# TiltMouseThroughHole.net
KiCad netlist of a schematic drawn in EAGLE
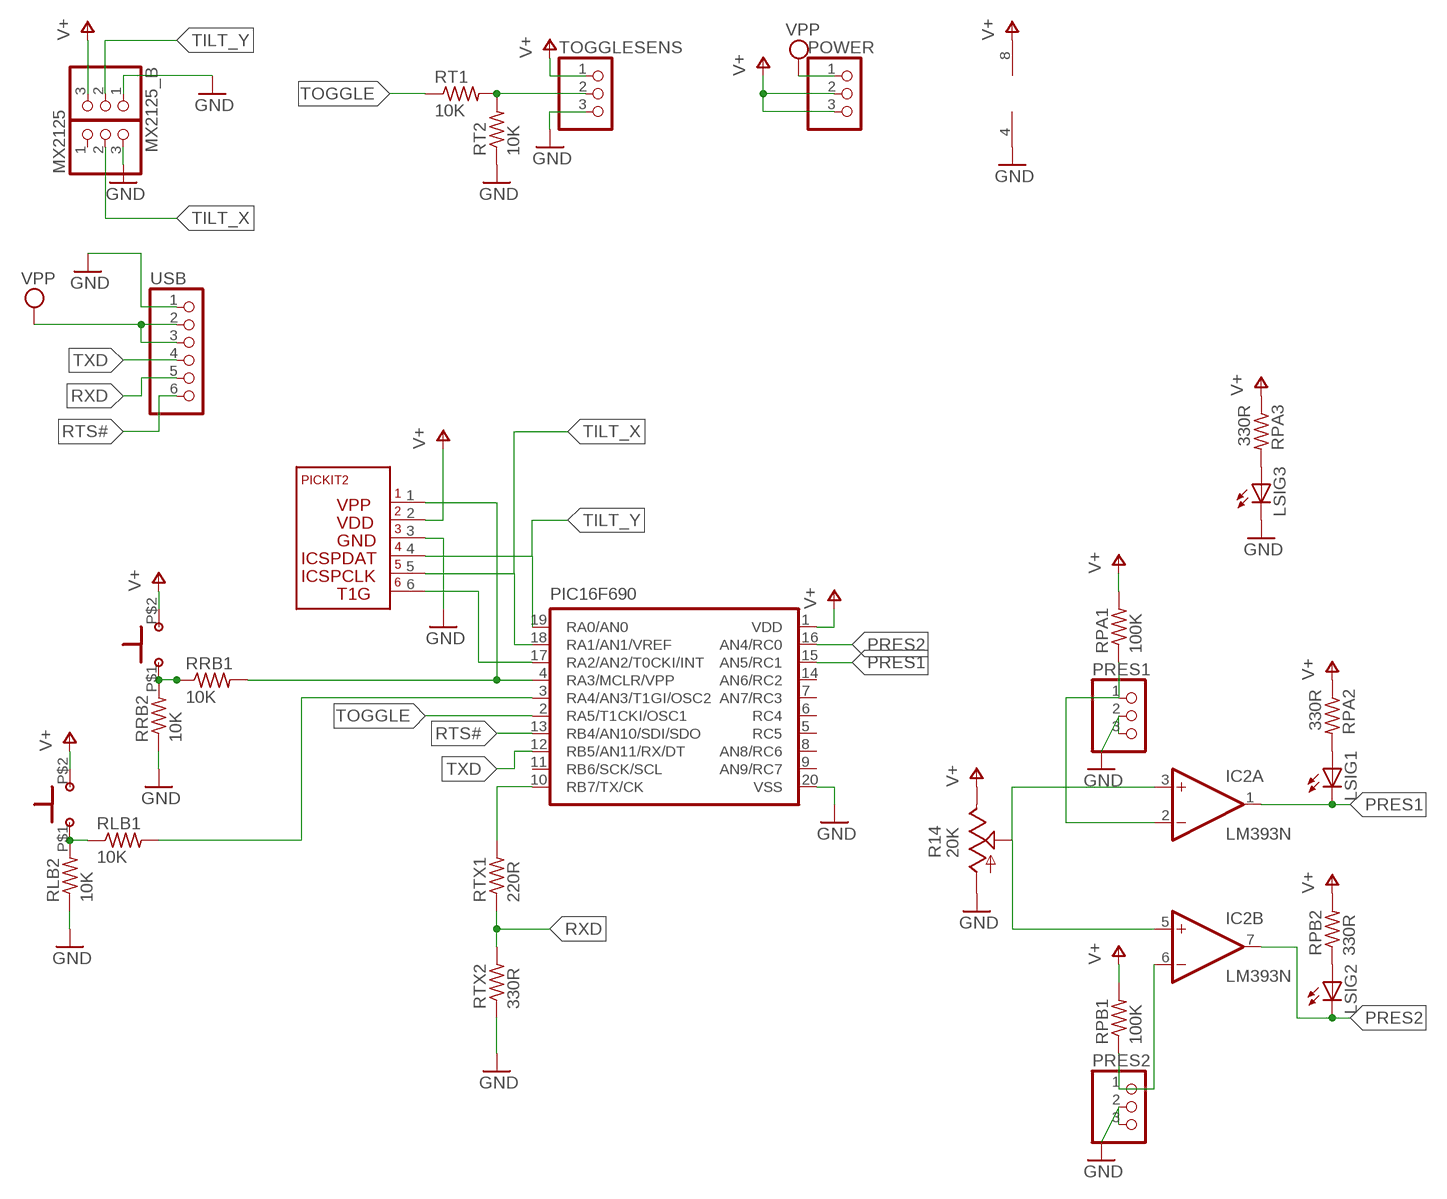
[diagram p0: schematic, sheet 1]

(export (version "E")
  (design (tool "Eeschema 10.0.6"))
  (components
    (comp (ref "IC2")
      (value "LM393N")
      (footprint "eagle-import:DIL08")
      (libsource (lib "eagle-import") (part "LM393N"))
    )
    (comp (ref "LB")
      (value "PUSHBUTTON")
      (footprint "eagle-import:PUSHBUTTON")
      (libsource (lib "eagle-import") (part "PUSHBUTTON"))
    )
    (comp (ref "LSIG1")
      (value "LED5MM")
      (footprint "eagle-import:LED5MM")
      (libsource (lib "eagle-import") (part "LED5MM"))
    )
    (comp (ref "LSIG2")
      (value "LED5MM")
      (footprint "eagle-import:LED5MM")
      (libsource (lib "eagle-import") (part "LED5MM"))
    )
    (comp (ref "LSIG3")
      (value "LED5MM")
      (footprint "eagle-import:LED5MM")
      (libsource (lib "eagle-import") (part "LED5MM"))
    )
    (comp (ref "MX2125")
      (value "PINHD-1X3")
      (footprint "eagle-import:1X03")
      (libsource (lib "eagle-import") (part "PINHD-1X3"))
    )
    (comp (ref "MX2125_B")
      (value "PINHD-1X3")
      (footprint "eagle-import:1X03")
      (libsource (lib "eagle-import") (part "PINHD-1X3"))
    )
    (comp (ref "PIC16F690")
      (value "PIC16F6XX")
      (footprint "eagle-import:DIL20")
      (libsource (lib "eagle-import") (part "PIC16F6XX"))
    )
    (comp (ref "POWER")
      (value "PINHD-1X3")
      (footprint "eagle-import:1X03")
      (libsource (lib "eagle-import") (part "PINHD-1X3"))
    )
    (comp (ref "PRES1")
      (value "PINHD-1X3/90")
      (footprint "eagle-import:1X03_90")
      (libsource (lib "eagle-import") (part "PINHD-1X3/90"))
    )
    (comp (ref "PRES2")
      (value "PINHD-1X3/90")
      (footprint "eagle-import:1X03_90")
      (libsource (lib "eagle-import") (part "PINHD-1X3/90"))
    )
    (comp (ref "R14")
      (value "20K")
      (footprint "eagle-import:B25P")
      (libsource (lib "eagle-import") (part "TRIM_US-B25P"))
    )
    (comp (ref "RB")
      (value "PUSHBUTTON")
      (footprint "eagle-import:PUSHBUTTON")
      (libsource (lib "eagle-import") (part "PUSHBUTTON"))
    )
    (comp (ref "RLB1")
      (value "10K")
      (footprint "eagle-import:0207_12")
      (libsource (lib "eagle-import") (part "R-US_0207/12"))
    )
    (comp (ref "RLB2")
      (value "10K")
      (footprint "eagle-import:0207_12")
      (libsource (lib "eagle-import") (part "R-US_0207/12"))
    )
    (comp (ref "RPA1")
      (value "100K")
      (footprint "eagle-import:0207_10")
      (libsource (lib "eagle-import") (part "R-US_0207/10"))
    )
    (comp (ref "RPA2")
      (value "330R")
      (footprint "eagle-import:0207_15")
      (libsource (lib "eagle-import") (part "R-US_0207/15"))
    )
    (comp (ref "RPA3")
      (value "330R")
      (footprint "eagle-import:0207_10")
      (libsource (lib "eagle-import") (part "R-US_0207/10"))
    )
    (comp (ref "RPB1")
      (value "100K")
      (footprint "eagle-import:0207_10")
      (libsource (lib "eagle-import") (part "R-US_0207/10"))
    )
    (comp (ref "RPB2")
      (value "330R")
      (footprint "eagle-import:0207_15")
      (libsource (lib "eagle-import") (part "R-US_0207/15"))
    )
    (comp (ref "RRB1")
      (value "10K")
      (footprint "eagle-import:0207_12")
      (libsource (lib "eagle-import") (part "R-US_0207/12"))
    )
    (comp (ref "RRB2")
      (value "10K")
      (footprint "eagle-import:0207_12")
      (libsource (lib "eagle-import") (part "R-US_0207/12"))
    )
    (comp (ref "RT1")
      (value "10K")
      (footprint "eagle-import:0207_10")
      (libsource (lib "eagle-import") (part "R-US_0207/10"))
    )
    (comp (ref "RT2")
      (value "10K")
      (footprint "eagle-import:0207_10")
      (libsource (lib "eagle-import") (part "R-US_0207/10"))
    )
    (comp (ref "RTX1")
      (value "220R")
      (footprint "eagle-import:0207_15")
      (libsource (lib "eagle-import") (part "R-US_0207/15"))
    )
    (comp (ref "RTX2")
      (value "330R")
      (footprint "eagle-import:0207_15")
      (libsource (lib "eagle-import") (part "R-US_0207/15"))
    )
    (comp (ref "TOGGLESENS")
      (value "PINHD-1X3")
      (footprint "eagle-import:1X03")
      (libsource (lib "eagle-import") (part "PINHD-1X3"))
    )
    (comp (ref "U$1")
      (value "PICKIT-ICSP")
      (footprint "eagle-import:PICKITJUMPER")
      (libsource (lib "eagle-import") (part "PICKIT-ICSP"))
    )
    (comp (ref "USB")
      (value "PINHD-1X6/90")
      (footprint "eagle-import:1X06_90")
      (libsource (lib "eagle-import") (part "PINHD-1X6/90"))
    )
  )
  (nets
    (net (code "1") (name "GND") (class "Default")
      (node (ref "IC2") (pin "4") (pinfunction "V-_4") (pintype "power_in"))
      (node (ref "LSIG3") (pin "K") (pinfunction "C_K") (pintype "passive"))
      (node (ref "MX2125") (pin "3") (pinfunction "3_3") (pintype "passive"))
      (node (ref "MX2125_B") (pin "1") (pinfunction "1_1") (pintype "passive"))
      (node (ref "PIC16F690") (pin "20") (pinfunction "VSS_20") (pintype "power_in"))
      (node (ref "PRES1") (pin "2") (pinfunction "2_2") (pintype "passive"))
      (node (ref "PRES1") (pin "3") (pinfunction "3_3") (pintype "passive"))
      (node (ref "PRES2") (pin "2") (pinfunction "2_2") (pintype "passive"))
      (node (ref "PRES2") (pin "3") (pinfunction "3_3") (pintype "passive"))
      (node (ref "R14") (pin "A") (pinfunction "A_A") (pintype "passive"))
      (node (ref "RLB2") (pin "1") (pinfunction "1_1") (pintype "passive"))
      (node (ref "RRB2") (pin "1") (pinfunction "1_1") (pintype "passive"))
      (node (ref "RT2") (pin "1") (pinfunction "1_1") (pintype "passive"))
      (node (ref "RTX2") (pin "1") (pinfunction "1_1") (pintype "passive"))
      (node (ref "TOGGLESENS") (pin "3") (pinfunction "3_3") (pintype "passive"))
      (node (ref "U$1") (pin "3") (pinfunction "P$3_3") (pintype "bidirectional"))
      (node (ref "USB") (pin "1") (pinfunction "1_1") (pintype "passive"))
    )
    (net (code "2") (name "Net-(IC2A-+IN)") (class "Default")
      (node (ref "IC2") (pin "3") (pinfunction "+IN_3") (pintype "input"))
      (node (ref "IC2") (pin "5") (pinfunction "+IN_5") (pintype "input"))
      (node (ref "R14") (pin "S") (pinfunction "S_S") (pintype "passive"))
    )
    (net (code "3") (name "Net-(IC2A--IN)") (class "Default")
      (node (ref "IC2") (pin "2") (pinfunction "-IN_2") (pintype "input"))
      (node (ref "PRES1") (pin "1") (pinfunction "1_1") (pintype "passive"))
      (node (ref "RPA1") (pin "1") (pinfunction "1_1") (pintype "passive"))
    )
    (net (code "4") (name "Net-(IC2B--IN)") (class "Default")
      (node (ref "IC2") (pin "6") (pinfunction "-IN_6") (pintype "input"))
      (node (ref "PRES2") (pin "1") (pinfunction "1_1") (pintype "passive"))
      (node (ref "RPB1") (pin "1") (pinfunction "1_1") (pintype "passive"))
    )
    (net (code "5") (name "Net-(LB-1)") (class "Default")
      (node (ref "LB") (pin "P$1") (pinfunction "1_P$1") (pintype "bidirectional"))
      (node (ref "RLB1") (pin "1") (pinfunction "1_1") (pintype "passive"))
      (node (ref "RLB2") (pin "2") (pinfunction "2_2") (pintype "passive"))
    )
    (net (code "6") (name "Net-(LSIG1-PadA)") (class "Default")
      (node (ref "LSIG1") (pin "A") (pinfunction "A_A") (pintype "passive"))
      (node (ref "RPA2") (pin "2") (pinfunction "2_2") (pintype "passive"))
    )
    (net (code "7") (name "Net-(LSIG2-PadA)") (class "Default")
      (node (ref "LSIG2") (pin "A") (pinfunction "A_A") (pintype "passive"))
      (node (ref "RPB2") (pin "1") (pinfunction "1_1") (pintype "passive"))
    )
    (net (code "8") (name "Net-(LSIG3-PadA)") (class "Default")
      (node (ref "LSIG3") (pin "A") (pinfunction "A_A") (pintype "passive"))
      (node (ref "RPA3") (pin "2") (pinfunction "2_2") (pintype "passive"))
    )
    (net (code "9") (name "Net-(PIC16F690-RA2{slash}AN2{slash}T0CKI{slash}INT)") (class "Default")
      (node (ref "PIC16F690") (pin "17") (pinfunction "RA2/AN2/T0CKI/INT_17") (pintype "bidirectional"))
      (node (ref "U$1") (pin "6") (pinfunction "P$6_6") (pintype "bidirectional"))
    )
    (net (code "10") (name "Net-(PIC16F690-RA3{slash}MCLR{slash}VPP)") (class "Default")
      (node (ref "PIC16F690") (pin "4") (pinfunction "RA3/MCLR/VPP_4") (pintype "input"))
      (node (ref "RRB1") (pin "2") (pinfunction "2_2") (pintype "passive"))
      (node (ref "U$1") (pin "1") (pinfunction "1_1") (pintype "bidirectional"))
    )
    (net (code "11") (name "Net-(PIC16F690-RA4{slash}AN3{slash}T1GI{slash}OSC2)") (class "Default")
      (node (ref "PIC16F690") (pin "3") (pinfunction "RA4/AN3/T1GI/OSC2_3") (pintype "bidirectional"))
      (node (ref "RLB1") (pin "2") (pinfunction "2_2") (pintype "passive"))
    )
    (net (code "12") (name "Net-(PIC16F690-RB7{slash}TX{slash}CK)") (class "Default")
      (node (ref "PIC16F690") (pin "10") (pinfunction "RB7/TX/CK_10") (pintype "bidirectional"))
      (node (ref "RTX1") (pin "2") (pinfunction "2_2") (pintype "passive"))
    )
    (net (code "13") (name "Net-(RB-1)") (class "Default")
      (node (ref "RB") (pin "P$1") (pinfunction "1_P$1") (pintype "bidirectional"))
      (node (ref "RRB1") (pin "1") (pinfunction "1_1") (pintype "passive"))
      (node (ref "RRB2") (pin "2") (pinfunction "2_2") (pintype "passive"))
    )
    (net (code "14") (name "Net-(RT1-Pad2)") (class "Default")
      (node (ref "RT1") (pin "2") (pinfunction "2_2") (pintype "passive"))
      (node (ref "RT2") (pin "2") (pinfunction "2_2") (pintype "passive"))
      (node (ref "TOGGLESENS") (pin "2") (pinfunction "2_2") (pintype "passive"))
    )
    (net (code "15") (name "PRES1") (class "Default")
      (node (ref "IC2") (pin "1") (pinfunction "OUT_1") (pintype "output"))
      (node (ref "LSIG1") (pin "K") (pinfunction "C_K") (pintype "passive"))
      (node (ref "PIC16F690") (pin "15") (pinfunction "AN5/RC1_15") (pintype "bidirectional"))
    )
    (net (code "16") (name "PRES2") (class "Default")
      (node (ref "IC2") (pin "7") (pinfunction "OUT_7") (pintype "output"))
      (node (ref "LSIG2") (pin "K") (pinfunction "C_K") (pintype "passive"))
      (node (ref "PIC16F690") (pin "16") (pinfunction "AN4/RC0_16") (pintype "bidirectional"))
    )
    (net (code "17") (name "RTS#") (class "Default")
      (node (ref "PIC16F690") (pin "13") (pinfunction "RB4/AN10/SDI/SDO_13") (pintype "bidirectional"))
      (node (ref "USB") (pin "6") (pinfunction "6_6") (pintype "passive"))
    )
    (net (code "18") (name "RXD") (class "Default")
      (node (ref "RTX1") (pin "1") (pinfunction "1_1") (pintype "passive"))
      (node (ref "RTX2") (pin "2") (pinfunction "2_2") (pintype "passive"))
      (node (ref "USB") (pin "5") (pinfunction "5_5") (pintype "passive"))
    )
    (net (code "19") (name "TILT_X") (class "Default")
      (node (ref "MX2125") (pin "2") (pinfunction "2_2") (pintype "passive"))
      (node (ref "PIC16F690") (pin "18") (pinfunction "RA1/AN1/VREF_18") (pintype "bidirectional"))
      (node (ref "U$1") (pin "5") (pinfunction "P$5_5") (pintype "bidirectional"))
    )
    (net (code "20") (name "TILT_Y") (class "Default")
      (node (ref "MX2125_B") (pin "2") (pinfunction "2_2") (pintype "passive"))
      (node (ref "PIC16F690") (pin "19") (pinfunction "RA0/AN0_19") (pintype "bidirectional"))
      (node (ref "U$1") (pin "4") (pinfunction "P$4_4") (pintype "bidirectional"))
    )
    (net (code "21") (name "TOGGLE") (class "Default")
      (node (ref "PIC16F690") (pin "2") (pinfunction "RA5/T1CKI/OSC1_2") (pintype "bidirectional"))
      (node (ref "RT1") (pin "1") (pinfunction "1_1") (pintype "passive"))
    )
    (net (code "22") (name "TXD") (class "Default")
      (node (ref "PIC16F690") (pin "12") (pinfunction "RB5/AN11/RX/DT_12") (pintype "bidirectional"))
      (node (ref "USB") (pin "4") (pinfunction "4_4") (pintype "passive"))
    )
    (net (code "23") (name "V+") (class "Default")
      (node (ref "IC2") (pin "8") (pinfunction "V+_8") (pintype "power_in"))
      (node (ref "LB") (pin "P$2") (pinfunction "2_P$2") (pintype "bidirectional"))
      (node (ref "MX2125_B") (pin "3") (pinfunction "3_3") (pintype "passive"))
      (node (ref "PIC16F690") (pin "1") (pinfunction "VDD_1") (pintype "power_in"))
      (node (ref "POWER") (pin "2") (pinfunction "2_2") (pintype "passive"))
      (node (ref "POWER") (pin "3") (pinfunction "3_3") (pintype "passive"))
      (node (ref "R14") (pin "E") (pinfunction "E_E") (pintype "passive"))
      (node (ref "RB") (pin "P$2") (pinfunction "2_P$2") (pintype "bidirectional"))
      (node (ref "RPA1") (pin "2") (pinfunction "2_2") (pintype "passive"))
      (node (ref "RPA2") (pin "1") (pinfunction "1_1") (pintype "passive"))
      (node (ref "RPA3") (pin "1") (pinfunction "1_1") (pintype "passive"))
      (node (ref "RPB1") (pin "2") (pinfunction "2_2") (pintype "passive"))
      (node (ref "RPB2") (pin "2") (pinfunction "2_2") (pintype "passive"))
      (node (ref "TOGGLESENS") (pin "1") (pinfunction "1_1") (pintype "passive"))
      (node (ref "U$1") (pin "2") (pinfunction "P$2_2") (pintype "bidirectional"))
    )
    (net (code "24") (name "VPP") (class "Default")
      (node (ref "POWER") (pin "1") (pinfunction "1_1") (pintype "passive"))
      (node (ref "USB") (pin "2") (pinfunction "2_2") (pintype "passive"))
      (node (ref "USB") (pin "3") (pinfunction "3_3") (pintype "passive"))
    )
    (net (code "25") (name "unconnected-(MX2125-Pad1)") (class "Default")
      (node (ref "MX2125") (pin "1") (pinfunction "1_1") (pintype "passive"))
    )
    (net (code "26") (name "unconnected-(PIC16F690-AN6{slash}RC2-Pad14)") (class "Default")
      (node (ref "PIC16F690") (pin "14") (pinfunction "AN6/RC2_14") (pintype "bidirectional"))
    )
    (net (code "27") (name "unconnected-(PIC16F690-AN7{slash}RC3-Pad7)") (class "Default")
      (node (ref "PIC16F690") (pin "7") (pinfunction "AN7/RC3_7") (pintype "bidirectional"))
    )
    (net (code "28") (name "unconnected-(PIC16F690-AN8{slash}RC6-Pad8)") (class "Default")
      (node (ref "PIC16F690") (pin "8") (pinfunction "AN8/RC6_8") (pintype "bidirectional"))
    )
    (net (code "29") (name "unconnected-(PIC16F690-AN9{slash}RC7-Pad9)") (class "Default")
      (node (ref "PIC16F690") (pin "9") (pinfunction "AN9/RC7_9") (pintype "bidirectional"))
    )
    (net (code "30") (name "unconnected-(PIC16F690-RB6{slash}SCK{slash}SCL-Pad11)") (class "Default")
      (node (ref "PIC16F690") (pin "11") (pinfunction "RB6/SCK/SCL_11") (pintype "bidirectional"))
    )
    (net (code "31") (name "unconnected-(PIC16F690-RC4-Pad6)") (class "Default")
      (node (ref "PIC16F690") (pin "6") (pinfunction "RC4_6") (pintype "bidirectional"))
    )
    (net (code "32") (name "unconnected-(PIC16F690-RC5-Pad5)") (class "Default")
      (node (ref "PIC16F690") (pin "5") (pinfunction "RC5_5") (pintype "bidirectional"))
    )
  )
)
